# Power.net
KiCad netlist of a schematic drawn in Altium Designer
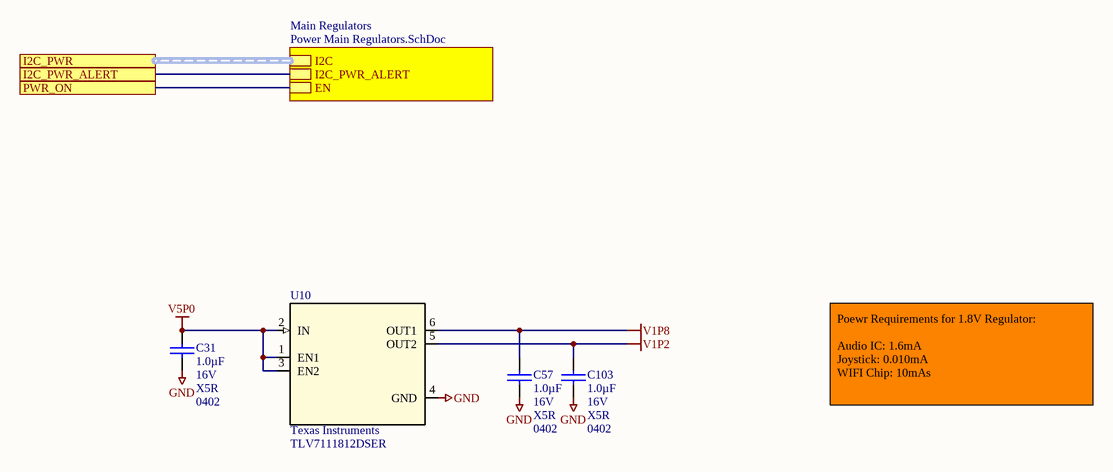
[diagram p0: Power.SchDoc]

(export (version "E")
  (design (tool "Eeschema 10.0.6"))
  (components
    (comp (ref "C31")
      (value "1.0uF")
      (footprint "C_0402")
      (description "CAP CER 1.0UF 16V X5R 0402")
      (fields
        (field (name "TOLERANCE") "10%")
        (field (name "CAPACITANCE") "1.0µF")
        (field (name "VOLTAGE - RATED") "16V")
        (field (name "TEMPERATURE COEFFICIENT") "X5R")
        (field (name "PACKAGE / CASE") "0402")
        (field (name "VOLTAGE") "16V")
      )
      (libsource (lib "Main LibraryX") (part "C_0402_1.0UF_16V"))
    )
    (comp (ref "C57")
      (value "1.0uF")
      (footprint "C_0402")
      (description "CAP CER 1.0UF 16V X5R 0402")
      (fields
        (field (name "TOLERANCE") "10%")
        (field (name "CAPACITANCE") "1.0µF")
        (field (name "VOLTAGE - RATED") "16V")
        (field (name "TEMPERATURE COEFFICIENT") "X5R")
        (field (name "PACKAGE / CASE") "0402")
        (field (name "VOLTAGE") "16V")
      )
      (libsource (lib "Main LibraryX") (part "C_0402_1.0UF_16V"))
    )
    (comp (ref "C103")
      (value "1.0uF")
      (footprint "C_0402")
      (description "CAP CER 1.0UF 16V X5R 0402")
      (fields
        (field (name "TOLERANCE") "10%")
        (field (name "CAPACITANCE") "1.0µF")
        (field (name "VOLTAGE - RATED") "16V")
        (field (name "TEMPERATURE COEFFICIENT") "X5R")
        (field (name "PACKAGE / CASE") "0402")
        (field (name "VOLTAGE") "16V")
      )
      (libsource (lib "Main LibraryX") (part "C_0402_1.0UF_16V"))
    )
    (comp (ref "U10")
      (value "U_TLV7111812DSER")
      (footprint "DSE6")
      (description "IC REG LDO 1.8V/1.2V 0.2A 6WSON")
      (fields
        (field (name "MANUFACTURER_PART_NUMBER") "TLV7111812DSER")
        (field (name "MANUFACTURER 1") "Texas Instruments")
        (field (name "MANUFACTURER PART NUMBER 1") "TLV7111812DSER")
      )
      (libsource (lib "Cospan Design") (part "U_TLV7111812DSER"))
    )
  )
  (nets
    (net (code "6") (name "GND") (class "Default")
      (node (ref "C103") (pin "1") (pinfunction "1_1") (pintype "passive"))
      (node (ref "C31") (pin "1") (pinfunction "1_1") (pintype "passive"))
      (node (ref "C57") (pin "1") (pinfunction "1_1") (pintype "passive"))
      (node (ref "U10") (pin "4") (pinfunction "GND_4") (pintype "power_in"))
    )
    (net (code "7") (name "V1P2") (class "Default")
      (node (ref "C103") (pin "2") (pinfunction "2_2") (pintype "passive"))
      (node (ref "U10") (pin "5") (pinfunction "OUT2_5") (pintype "power_in"))
    )
    (net (code "8") (name "V1P8") (class "Default")
      (node (ref "C57") (pin "2") (pinfunction "2_2") (pintype "passive"))
      (node (ref "U10") (pin "6") (pinfunction "OUT1_6") (pintype "power_in"))
    )
    (net (code "9") (name "V5P0") (class "Default")
      (node (ref "C31") (pin "2") (pinfunction "2_2") (pintype "passive"))
      (node (ref "U10") (pin "1") (pinfunction "EN1_1") (pintype "passive"))
      (node (ref "U10") (pin "2") (pinfunction "IN_2") (pintype "input"))
      (node (ref "U10") (pin "3") (pinfunction "EN2_3") (pintype "passive"))
    )
  )
)
